# control_board.net
KiCad netlist of a schematic drawn in EAGLE
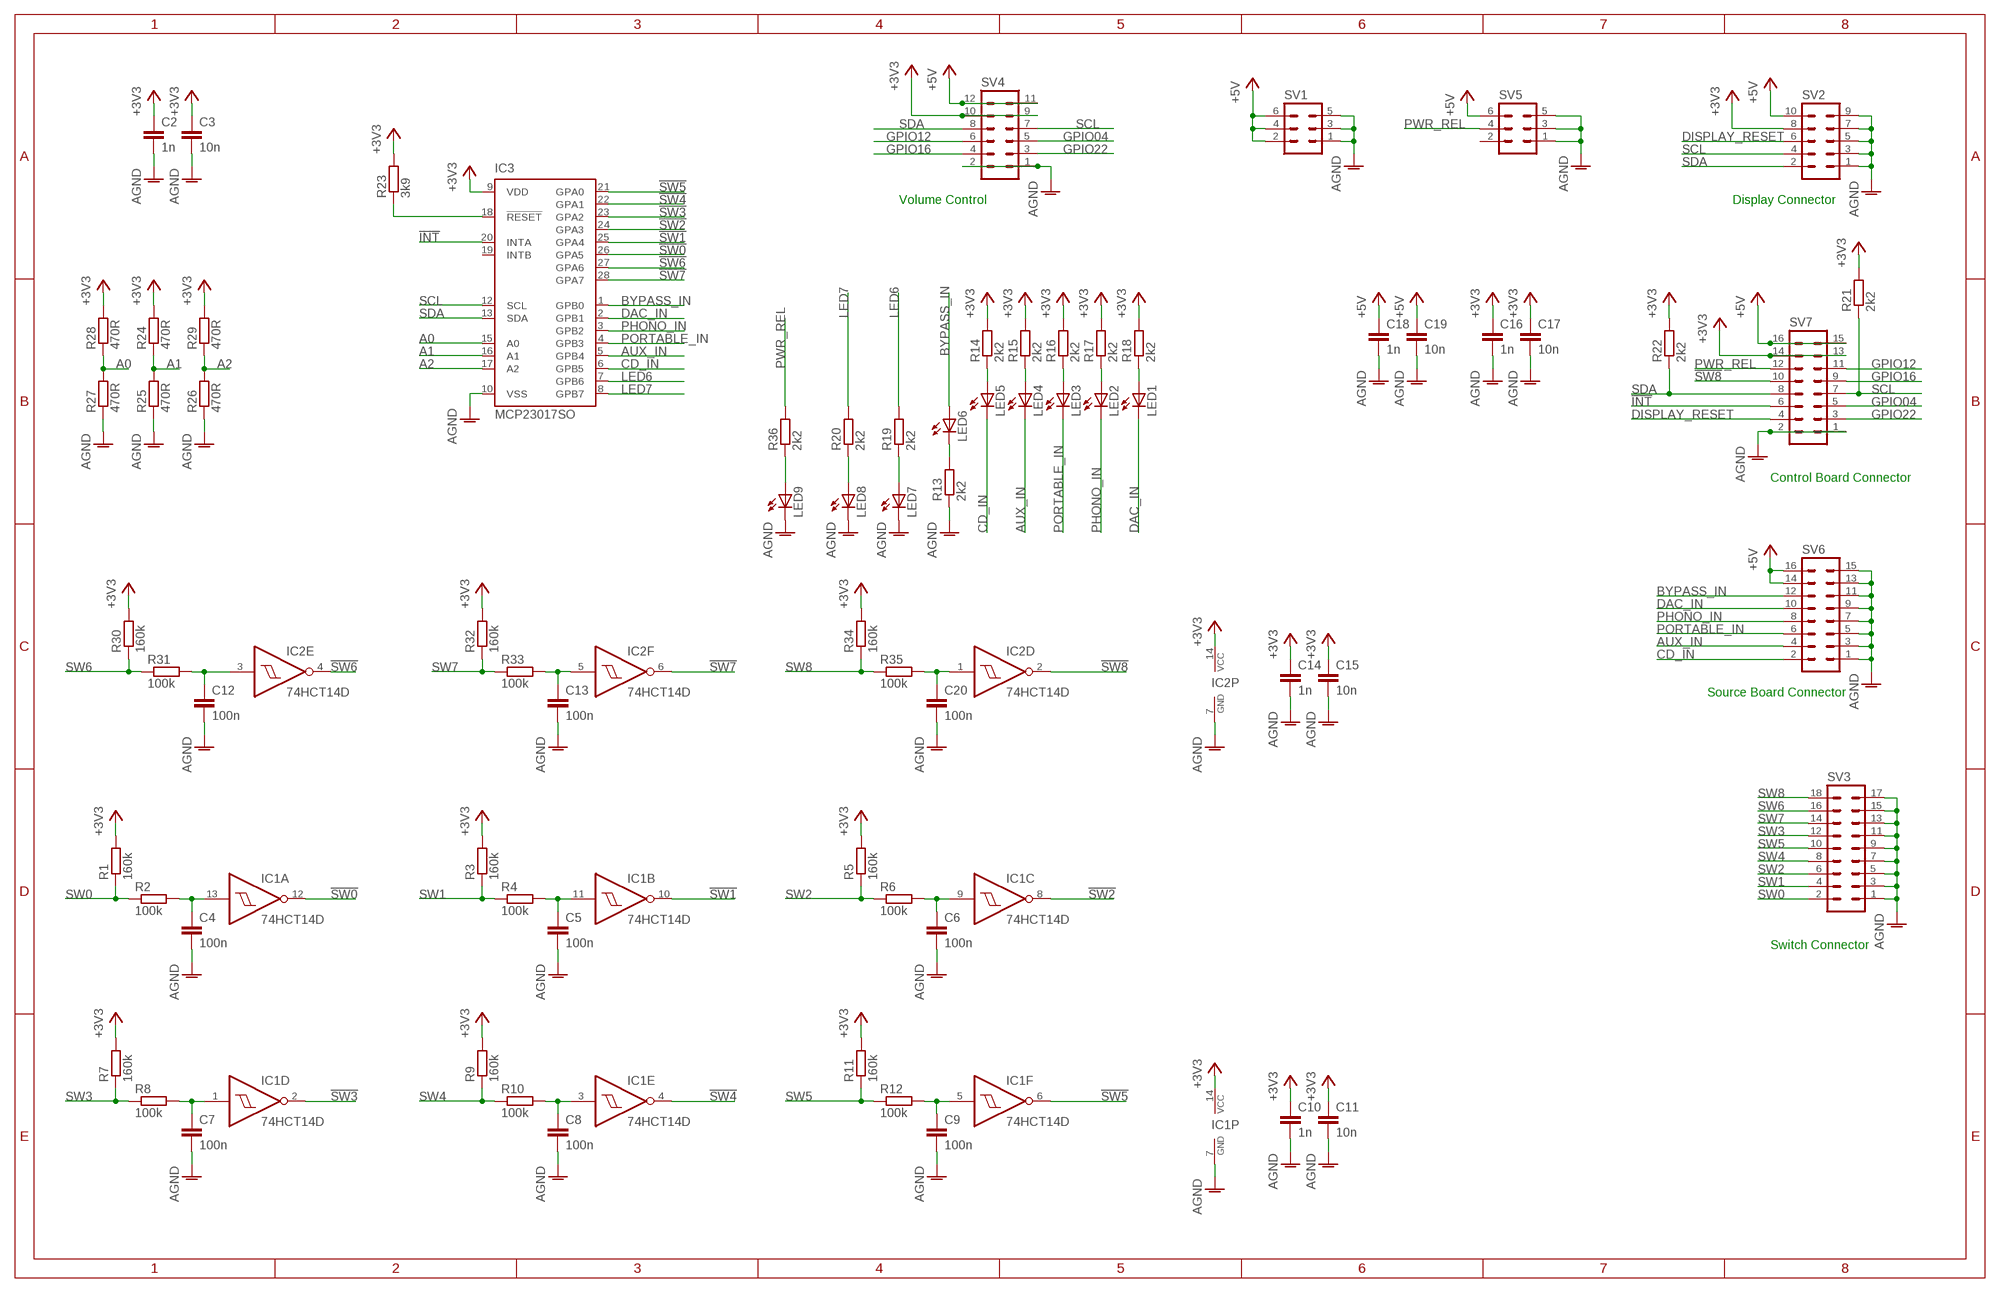
[diagram p0: schematic, sheet 1]

(export (version "E")
  (design (tool "Eeschema 10.0.6"))
  (components
    (comp (ref "C2")
      (value "1n")
      (footprint "eagle-import:C0603")
      (libsource (lib "eagle-import") (part "C-EUC0603"))
    )
    (comp (ref "C3")
      (value "10n")
      (footprint "eagle-import:C0603")
      (libsource (lib "eagle-import") (part "C-EUC0603"))
    )
    (comp (ref "C4")
      (value "100n")
      (footprint "eagle-import:C0603")
      (libsource (lib "eagle-import") (part "C-EUC0603"))
    )
    (comp (ref "C5")
      (value "100n")
      (footprint "eagle-import:C0603")
      (libsource (lib "eagle-import") (part "C-EUC0603"))
    )
    (comp (ref "C6")
      (value "100n")
      (footprint "eagle-import:C0603")
      (libsource (lib "eagle-import") (part "C-EUC0603"))
    )
    (comp (ref "C7")
      (value "100n")
      (footprint "eagle-import:C0603")
      (libsource (lib "eagle-import") (part "C-EUC0603"))
    )
    (comp (ref "C8")
      (value "100n")
      (footprint "eagle-import:C0603")
      (libsource (lib "eagle-import") (part "C-EUC0603"))
    )
    (comp (ref "C9")
      (value "100n")
      (footprint "eagle-import:C0603")
      (libsource (lib "eagle-import") (part "C-EUC0603"))
    )
    (comp (ref "C10")
      (value "1n")
      (footprint "eagle-import:C0603")
      (libsource (lib "eagle-import") (part "C-EUC0603"))
    )
    (comp (ref "C11")
      (value "10n")
      (footprint "eagle-import:C0603")
      (libsource (lib "eagle-import") (part "C-EUC0603"))
    )
    (comp (ref "C12")
      (value "100n")
      (footprint "eagle-import:C0603")
      (libsource (lib "eagle-import") (part "C-EUC0603"))
    )
    (comp (ref "C13")
      (value "100n")
      (footprint "eagle-import:C0603")
      (libsource (lib "eagle-import") (part "C-EUC0603"))
    )
    (comp (ref "C14")
      (value "1n")
      (footprint "eagle-import:C0603")
      (libsource (lib "eagle-import") (part "C-EUC0603"))
    )
    (comp (ref "C15")
      (value "10n")
      (footprint "eagle-import:C0603")
      (libsource (lib "eagle-import") (part "C-EUC0603"))
    )
    (comp (ref "C16")
      (value "1n")
      (footprint "eagle-import:C0603")
      (libsource (lib "eagle-import") (part "C-EUC0603"))
    )
    (comp (ref "C17")
      (value "10n")
      (footprint "eagle-import:C0603")
      (libsource (lib "eagle-import") (part "C-EUC0603"))
    )
    (comp (ref "C18")
      (value "1n")
      (footprint "eagle-import:C0603")
      (libsource (lib "eagle-import") (part "C-EUC0603"))
    )
    (comp (ref "C19")
      (value "10n")
      (footprint "eagle-import:C0603")
      (libsource (lib "eagle-import") (part "C-EUC0603"))
    )
    (comp (ref "C20")
      (value "100n")
      (footprint "eagle-import:C0603")
      (libsource (lib "eagle-import") (part "C-EUC0603"))
    )
    (comp (ref "IC1")
      (value "74HCT14D")
      (footprint "eagle-import:SO14")
      (libsource (lib "eagle-import") (part "7414DHCT"))
    )
    (comp (ref "IC2")
      (value "74HCT14D")
      (footprint "eagle-import:SO14")
      (libsource (lib "eagle-import") (part "7414DHCT"))
    )
    (comp (ref "IC3")
      (value "MCP23017SO")
      (footprint "eagle-import:SO28W")
      (fields (field (name "MF") "MICROCHIP") (field (name "MPN") "MCP23017-E/SO"))
      (libsource (lib "eagle-import") (part "MCP23017SO"))
    )
    (comp (ref "LED1")
      (value "LEDCHIPLED_0603")
      (footprint "eagle-import:CHIPLED_0603")
      (libsource (lib "eagle-import") (part "LEDCHIPLED_0603"))
    )
    (comp (ref "LED2")
      (value "LEDCHIPLED_0603")
      (footprint "eagle-import:CHIPLED_0603")
      (libsource (lib "eagle-import") (part "LEDCHIPLED_0603"))
    )
    (comp (ref "LED3")
      (value "LEDCHIPLED_0603")
      (footprint "eagle-import:CHIPLED_0603")
      (libsource (lib "eagle-import") (part "LEDCHIPLED_0603"))
    )
    (comp (ref "LED4")
      (value "LEDCHIPLED_0603")
      (footprint "eagle-import:CHIPLED_0603")
      (libsource (lib "eagle-import") (part "LEDCHIPLED_0603"))
    )
    (comp (ref "LED5")
      (value "LEDCHIPLED_0603")
      (footprint "eagle-import:CHIPLED_0603")
      (libsource (lib "eagle-import") (part "LEDCHIPLED_0603"))
    )
    (comp (ref "LED6")
      (value "LEDCHIPLED_0603")
      (footprint "eagle-import:CHIPLED_0603")
      (libsource (lib "eagle-import") (part "LEDCHIPLED_0603"))
    )
    (comp (ref "LED7")
      (value "LEDCHIPLED_0603")
      (footprint "eagle-import:CHIPLED_0603")
      (libsource (lib "eagle-import") (part "LEDCHIPLED_0603"))
    )
    (comp (ref "LED8")
      (value "LEDCHIPLED_0603")
      (footprint "eagle-import:CHIPLED_0603")
      (libsource (lib "eagle-import") (part "LEDCHIPLED_0603"))
    )
    (comp (ref "LED9")
      (value "LEDCHIPLED_0603")
      (footprint "eagle-import:CHIPLED_0603")
      (libsource (lib "eagle-import") (part "LEDCHIPLED_0603"))
    )
    (comp (ref "R1")
      (value "160k")
      (footprint "eagle-import:R0603")
      (libsource (lib "eagle-import") (part "R-EU_R0603"))
    )
    (comp (ref "R2")
      (value "100k")
      (footprint "eagle-import:R0603")
      (libsource (lib "eagle-import") (part "R-EU_R0603"))
    )
    (comp (ref "R3")
      (value "160k")
      (footprint "eagle-import:R0603")
      (libsource (lib "eagle-import") (part "R-EU_R0603"))
    )
    (comp (ref "R4")
      (value "100k")
      (footprint "eagle-import:R0603")
      (libsource (lib "eagle-import") (part "R-EU_R0603"))
    )
    (comp (ref "R5")
      (value "160k")
      (footprint "eagle-import:R0603")
      (libsource (lib "eagle-import") (part "R-EU_R0603"))
    )
    (comp (ref "R6")
      (value "100k")
      (footprint "eagle-import:R0603")
      (libsource (lib "eagle-import") (part "R-EU_R0603"))
    )
    (comp (ref "R7")
      (value "160k")
      (footprint "eagle-import:R0603")
      (libsource (lib "eagle-import") (part "R-EU_R0603"))
    )
    (comp (ref "R8")
      (value "100k")
      (footprint "eagle-import:R0603")
      (libsource (lib "eagle-import") (part "R-EU_R0603"))
    )
    (comp (ref "R9")
      (value "160k")
      (footprint "eagle-import:R0603")
      (libsource (lib "eagle-import") (part "R-EU_R0603"))
    )
    (comp (ref "R10")
      (value "100k")
      (footprint "eagle-import:R0603")
      (libsource (lib "eagle-import") (part "R-EU_R0603"))
    )
    (comp (ref "R11")
      (value "160k")
      (footprint "eagle-import:R0603")
      (libsource (lib "eagle-import") (part "R-EU_R0603"))
    )
    (comp (ref "R12")
      (value "100k")
      (footprint "eagle-import:R0603")
      (libsource (lib "eagle-import") (part "R-EU_R0603"))
    )
    (comp (ref "R13")
      (value "2k2")
      (footprint "eagle-import:R0603")
      (libsource (lib "eagle-import") (part "R-EU_R0603"))
    )
    (comp (ref "R14")
      (value "2k2")
      (footprint "eagle-import:R0603")
      (libsource (lib "eagle-import") (part "R-EU_R0603"))
    )
    (comp (ref "R15")
      (value "2k2")
      (footprint "eagle-import:R0603")
      (libsource (lib "eagle-import") (part "R-EU_R0603"))
    )
    (comp (ref "R16")
      (value "2k2")
      (footprint "eagle-import:R0603")
      (libsource (lib "eagle-import") (part "R-EU_R0603"))
    )
    (comp (ref "R17")
      (value "2k2")
      (footprint "eagle-import:R0603")
      (libsource (lib "eagle-import") (part "R-EU_R0603"))
    )
    (comp (ref "R18")
      (value "2k2")
      (footprint "eagle-import:R0603")
      (libsource (lib "eagle-import") (part "R-EU_R0603"))
    )
    (comp (ref "R19")
      (value "2k2")
      (footprint "eagle-import:R0603")
      (libsource (lib "eagle-import") (part "R-EU_R0603"))
    )
    (comp (ref "R20")
      (value "2k2")
      (footprint "eagle-import:R0603")
      (libsource (lib "eagle-import") (part "R-EU_R0603"))
    )
    (comp (ref "R21")
      (value "2k2")
      (footprint "eagle-import:R0603")
      (libsource (lib "eagle-import") (part "R-EU_R0603"))
    )
    (comp (ref "R22")
      (value "2k2")
      (footprint "eagle-import:R0603")
      (libsource (lib "eagle-import") (part "R-EU_R0603"))
    )
    (comp (ref "R23")
      (value "3k9")
      (footprint "eagle-import:R0603")
      (libsource (lib "eagle-import") (part "R-EU_R0603"))
    )
    (comp (ref "R24")
      (value "470R")
      (footprint "eagle-import:R0603")
      (libsource (lib "eagle-import") (part "R-EU_R0603"))
    )
    (comp (ref "R25")
      (value "470R")
      (footprint "eagle-import:R0603")
      (libsource (lib "eagle-import") (part "R-EU_R0603"))
    )
    (comp (ref "R26")
      (value "470R")
      (footprint "eagle-import:R0603")
      (libsource (lib "eagle-import") (part "R-EU_R0603"))
    )
    (comp (ref "R27")
      (value "470R")
      (footprint "eagle-import:R0603")
      (libsource (lib "eagle-import") (part "R-EU_R0603"))
    )
    (comp (ref "R28")
      (value "470R")
      (footprint "eagle-import:R0603")
      (libsource (lib "eagle-import") (part "R-EU_R0603"))
    )
    (comp (ref "R29")
      (value "470R")
      (footprint "eagle-import:R0603")
      (libsource (lib "eagle-import") (part "R-EU_R0603"))
    )
    (comp (ref "R30")
      (value "160k")
      (footprint "eagle-import:R0603")
      (libsource (lib "eagle-import") (part "R-EU_R0603"))
    )
    (comp (ref "R31")
      (value "100k")
      (footprint "eagle-import:R0603")
      (libsource (lib "eagle-import") (part "R-EU_R0603"))
    )
    (comp (ref "R32")
      (value "160k")
      (footprint "eagle-import:R0603")
      (libsource (lib "eagle-import") (part "R-EU_R0603"))
    )
    (comp (ref "R33")
      (value "100k")
      (footprint "eagle-import:R0603")
      (libsource (lib "eagle-import") (part "R-EU_R0603"))
    )
    (comp (ref "R34")
      (value "160k")
      (footprint "eagle-import:R0603")
      (libsource (lib "eagle-import") (part "R-EU_R0603"))
    )
    (comp (ref "R35")
      (value "100k")
      (footprint "eagle-import:R0603")
      (libsource (lib "eagle-import") (part "R-EU_R0603"))
    )
    (comp (ref "R36")
      (value "2k2")
      (footprint "eagle-import:R0603")
      (libsource (lib "eagle-import") (part "R-EU_R0603"))
    )
    (comp (ref "SV1")
      (value "MA03-2")
      (footprint "eagle-import:MA03-2")
      (libsource (lib "eagle-import") (part "MA03-2"))
    )
    (comp (ref "SV2")
      (value "MA05-2")
      (footprint "eagle-import:MA05-2")
      (libsource (lib "eagle-import") (part "MA05-2"))
    )
    (comp (ref "SV3")
      (value "MA09-2")
      (footprint "eagle-import:MA09-2")
      (libsource (lib "eagle-import") (part "MA09-2"))
    )
    (comp (ref "SV4")
      (value "MA06-2")
      (footprint "eagle-import:MA06-2")
      (libsource (lib "eagle-import") (part "MA06-2"))
    )
    (comp (ref "SV5")
      (value "MA03-2")
      (footprint "eagle-import:MA03-2")
      (libsource (lib "eagle-import") (part "MA03-2"))
    )
    (comp (ref "SV6")
      (value "MA08-2")
      (footprint "eagle-import:MA08-2")
      (libsource (lib "eagle-import") (part "MA08-2"))
    )
    (comp (ref "SV7")
      (value "MA08-2")
      (footprint "eagle-import:MA08-2")
      (libsource (lib "eagle-import") (part "MA08-2"))
    )
  )
  (nets
    (net (code "1") (name "+3V3") (class "Default")
      (node (ref "C10") (pin "1") (pinfunction "1_1") (pintype "passive"))
      (node (ref "C11") (pin "1") (pinfunction "1_1") (pintype "passive"))
      (node (ref "C14") (pin "1") (pinfunction "1_1") (pintype "passive"))
      (node (ref "C15") (pin "1") (pinfunction "1_1") (pintype "passive"))
      (node (ref "C16") (pin "1") (pinfunction "1_1") (pintype "passive"))
      (node (ref "C17") (pin "1") (pinfunction "1_1") (pintype "passive"))
      (node (ref "C2") (pin "1") (pinfunction "1_1") (pintype "passive"))
      (node (ref "C3") (pin "1") (pinfunction "1_1") (pintype "passive"))
      (node (ref "IC1") (pin "14") (pinfunction "VCC_14") (pintype "power_in"))
      (node (ref "IC2") (pin "14") (pinfunction "VCC_14") (pintype "power_in"))
      (node (ref "IC3") (pin "9") (pinfunction "VDD_9") (pintype "power_in"))
      (node (ref "R1") (pin "2") (pinfunction "2_2") (pintype "passive"))
      (node (ref "R11") (pin "2") (pinfunction "2_2") (pintype "passive"))
      (node (ref "R14") (pin "2") (pinfunction "2_2") (pintype "passive"))
      (node (ref "R15") (pin "2") (pinfunction "2_2") (pintype "passive"))
      (node (ref "R16") (pin "2") (pinfunction "2_2") (pintype "passive"))
      (node (ref "R17") (pin "2") (pinfunction "2_2") (pintype "passive"))
      (node (ref "R18") (pin "2") (pinfunction "2_2") (pintype "passive"))
      (node (ref "R21") (pin "2") (pinfunction "2_2") (pintype "passive"))
      (node (ref "R22") (pin "2") (pinfunction "2_2") (pintype "passive"))
      (node (ref "R23") (pin "2") (pinfunction "2_2") (pintype "passive"))
      (node (ref "R24") (pin "2") (pinfunction "2_2") (pintype "passive"))
      (node (ref "R28") (pin "2") (pinfunction "2_2") (pintype "passive"))
      (node (ref "R29") (pin "2") (pinfunction "2_2") (pintype "passive"))
      (node (ref "R3") (pin "2") (pinfunction "2_2") (pintype "passive"))
      (node (ref "R30") (pin "2") (pinfunction "2_2") (pintype "passive"))
      (node (ref "R32") (pin "2") (pinfunction "2_2") (pintype "passive"))
      (node (ref "R34") (pin "2") (pinfunction "2_2") (pintype "passive"))
      (node (ref "R5") (pin "2") (pinfunction "2_2") (pintype "passive"))
      (node (ref "R7") (pin "2") (pinfunction "2_2") (pintype "passive"))
      (node (ref "R9") (pin "2") (pinfunction "2_2") (pintype "passive"))
      (node (ref "SV2") (pin "8") (pinfunction "8_8") (pintype "passive"))
      (node (ref "SV4") (pin "10") (pinfunction "10_10") (pintype "passive"))
      (node (ref "SV4") (pin "9") (pinfunction "9_9") (pintype "passive"))
      (node (ref "SV7") (pin "13") (pinfunction "13_13") (pintype "passive"))
      (node (ref "SV7") (pin "14") (pinfunction "14_14") (pintype "passive"))
    )
    (net (code "2") (name "+5V") (class "Default")
      (node (ref "C18") (pin "1") (pinfunction "1_1") (pintype "passive"))
      (node (ref "C19") (pin "1") (pinfunction "1_1") (pintype "passive"))
      (node (ref "SV1") (pin "2") (pinfunction "2_2") (pintype "passive"))
      (node (ref "SV1") (pin "4") (pinfunction "4_4") (pintype "passive"))
      (node (ref "SV1") (pin "6") (pinfunction "6_6") (pintype "passive"))
      (node (ref "SV2") (pin "10") (pinfunction "10_10") (pintype "passive"))
      (node (ref "SV4") (pin "11") (pinfunction "11_11") (pintype "passive"))
      (node (ref "SV4") (pin "12") (pinfunction "12_12") (pintype "passive"))
      (node (ref "SV5") (pin "6") (pinfunction "6_6") (pintype "passive"))
      (node (ref "SV6") (pin "14") (pinfunction "14_14") (pintype "passive"))
      (node (ref "SV6") (pin "16") (pinfunction "16_16") (pintype "passive"))
      (node (ref "SV7") (pin "15") (pinfunction "15_15") (pintype "passive"))
      (node (ref "SV7") (pin "16") (pinfunction "16_16") (pintype "passive"))
    )
    (net (code "3") (name "/A0") (class "Default")
      (node (ref "IC3") (pin "15") (pinfunction "A0_15") (pintype "input"))
      (node (ref "R27") (pin "2") (pinfunction "2_2") (pintype "passive"))
      (node (ref "R28") (pin "1") (pinfunction "1_1") (pintype "passive"))
    )
    (net (code "4") (name "/A1") (class "Default")
      (node (ref "IC3") (pin "16") (pinfunction "A1_16") (pintype "input"))
      (node (ref "R24") (pin "1") (pinfunction "1_1") (pintype "passive"))
      (node (ref "R25") (pin "2") (pinfunction "2_2") (pintype "passive"))
    )
    (net (code "5") (name "/A2") (class "Default")
      (node (ref "IC3") (pin "17") (pinfunction "A2_17") (pintype "input"))
      (node (ref "R26") (pin "2") (pinfunction "2_2") (pintype "passive"))
      (node (ref "R29") (pin "1") (pinfunction "1_1") (pintype "passive"))
    )
    (net (code "6") (name "/AUX_IN") (class "Default")
      (node (ref "IC3") (pin "5") (pinfunction "GPB4_5") (pintype "bidirectional"))
      (node (ref "LED4") (pin "C") (pinfunction "C_C") (pintype "passive"))
      (node (ref "SV6") (pin "4") (pinfunction "4_4") (pintype "passive"))
    )
    (net (code "7") (name "/BYPASS_IN") (class "Default")
      (node (ref "IC3") (pin "1") (pinfunction "GPB0_1") (pintype "bidirectional"))
      (node (ref "LED6") (pin "A") (pinfunction "A_A") (pintype "passive"))
      (node (ref "SV6") (pin "12") (pinfunction "12_12") (pintype "passive"))
    )
    (net (code "8") (name "/CD_IN") (class "Default")
      (node (ref "IC3") (pin "6") (pinfunction "GPB5_6") (pintype "bidirectional"))
      (node (ref "LED5") (pin "C") (pinfunction "C_C") (pintype "passive"))
      (node (ref "SV6") (pin "2") (pinfunction "2_2") (pintype "passive"))
    )
    (net (code "9") (name "/DAC_IN") (class "Default")
      (node (ref "IC3") (pin "2") (pinfunction "GPB1_2") (pintype "bidirectional"))
      (node (ref "LED1") (pin "C") (pinfunction "C_C") (pintype "passive"))
      (node (ref "SV6") (pin "10") (pinfunction "10_10") (pintype "passive"))
    )
    (net (code "10") (name "/DISPLAY_RESET") (class "Default")
      (node (ref "SV2") (pin "6") (pinfunction "6_6") (pintype "passive"))
      (node (ref "SV7") (pin "4") (pinfunction "4_4") (pintype "passive"))
    )
    (net (code "11") (name "/GPIO04") (class "Default")
      (node (ref "SV4") (pin "5") (pinfunction "5_5") (pintype "passive"))
      (node (ref "SV7") (pin "5") (pinfunction "5_5") (pintype "passive"))
    )
    (net (code "12") (name "/GPIO12") (class "Default")
      (node (ref "SV4") (pin "6") (pinfunction "6_6") (pintype "passive"))
      (node (ref "SV7") (pin "11") (pinfunction "11_11") (pintype "passive"))
    )
    (net (code "13") (name "/GPIO16") (class "Default")
      (node (ref "SV4") (pin "4") (pinfunction "4_4") (pintype "passive"))
      (node (ref "SV7") (pin "9") (pinfunction "9_9") (pintype "passive"))
    )
    (net (code "14") (name "/GPIO22") (class "Default")
      (node (ref "SV4") (pin "3") (pinfunction "3_3") (pintype "passive"))
      (node (ref "SV7") (pin "3") (pinfunction "3_3") (pintype "passive"))
    )
    (net (code "15") (name "/LED6") (class "Default")
      (node (ref "IC3") (pin "7") (pinfunction "GPB6_7") (pintype "bidirectional"))
      (node (ref "R19") (pin "2") (pinfunction "2_2") (pintype "passive"))
    )
    (net (code "16") (name "/LED7") (class "Default")
      (node (ref "IC3") (pin "8") (pinfunction "GPB7_8") (pintype "bidirectional"))
      (node (ref "R20") (pin "2") (pinfunction "2_2") (pintype "passive"))
    )
    (net (code "17") (name "/PHONO_IN") (class "Default")
      (node (ref "IC3") (pin "3") (pinfunction "GPB2_3") (pintype "bidirectional"))
      (node (ref "LED2") (pin "C") (pinfunction "C_C") (pintype "passive"))
      (node (ref "SV6") (pin "8") (pinfunction "8_8") (pintype "passive"))
    )
    (net (code "18") (name "/PORTABLE_IN") (class "Default")
      (node (ref "IC3") (pin "4") (pinfunction "GPB3_4") (pintype "bidirectional"))
      (node (ref "LED3") (pin "C") (pinfunction "C_C") (pintype "passive"))
      (node (ref "SV6") (pin "6") (pinfunction "6_6") (pintype "passive"))
    )
    (net (code "19") (name "/PWR_REL") (class "Default")
      (node (ref "R36") (pin "2") (pinfunction "2_2") (pintype "passive"))
      (node (ref "SV5") (pin "4") (pinfunction "4_4") (pintype "passive"))
      (node (ref "SV7") (pin "12") (pinfunction "12_12") (pintype "passive"))
    )
    (net (code "20") (name "/SCL") (class "Default")
      (node (ref "IC3") (pin "12") (pinfunction "SCL_12") (pintype "input"))
      (node (ref "R21") (pin "1") (pinfunction "1_1") (pintype "passive"))
      (node (ref "SV2") (pin "4") (pinfunction "4_4") (pintype "passive"))
      (node (ref "SV4") (pin "7") (pinfunction "7_7") (pintype "passive"))
      (node (ref "SV7") (pin "7") (pinfunction "7_7") (pintype "passive"))
    )
    (net (code "21") (name "/SDA") (class "Default")
      (node (ref "IC3") (pin "13") (pinfunction "SDA_13") (pintype "bidirectional"))
      (node (ref "R22") (pin "1") (pinfunction "1_1") (pintype "passive"))
      (node (ref "SV2") (pin "2") (pinfunction "2_2") (pintype "passive"))
      (node (ref "SV4") (pin "8") (pinfunction "8_8") (pintype "passive"))
      (node (ref "SV7") (pin "8") (pinfunction "8_8") (pintype "passive"))
    )
    (net (code "22") (name "/SW0") (class "Default")
      (node (ref "R1") (pin "1") (pinfunction "1_1") (pintype "passive"))
      (node (ref "R2") (pin "1") (pinfunction "1_1") (pintype "passive"))
      (node (ref "SV3") (pin "2") (pinfunction "2_2") (pintype "passive"))
    )
    (net (code "23") (name "/SW1") (class "Default")
      (node (ref "R3") (pin "1") (pinfunction "1_1") (pintype "passive"))
      (node (ref "R4") (pin "1") (pinfunction "1_1") (pintype "passive"))
      (node (ref "SV3") (pin "4") (pinfunction "4_4") (pintype "passive"))
    )
    (net (code "24") (name "/SW2") (class "Default")
      (node (ref "R5") (pin "1") (pinfunction "1_1") (pintype "passive"))
      (node (ref "R6") (pin "1") (pinfunction "1_1") (pintype "passive"))
      (node (ref "SV3") (pin "6") (pinfunction "6_6") (pintype "passive"))
    )
    (net (code "25") (name "/SW3") (class "Default")
      (node (ref "R7") (pin "1") (pinfunction "1_1") (pintype "passive"))
      (node (ref "R8") (pin "1") (pinfunction "1_1") (pintype "passive"))
      (node (ref "SV3") (pin "12") (pinfunction "12_12") (pintype "passive"))
    )
    (net (code "26") (name "/SW4") (class "Default")
      (node (ref "R10") (pin "1") (pinfunction "1_1") (pintype "passive"))
      (node (ref "R9") (pin "1") (pinfunction "1_1") (pintype "passive"))
      (node (ref "SV3") (pin "8") (pinfunction "8_8") (pintype "passive"))
    )
    (net (code "27") (name "/SW5") (class "Default")
      (node (ref "R11") (pin "1") (pinfunction "1_1") (pintype "passive"))
      (node (ref "R12") (pin "1") (pinfunction "1_1") (pintype "passive"))
      (node (ref "SV3") (pin "10") (pinfunction "10_10") (pintype "passive"))
    )
    (net (code "28") (name "/SW6") (class "Default")
      (node (ref "R30") (pin "1") (pinfunction "1_1") (pintype "passive"))
      (node (ref "R31") (pin "1") (pinfunction "1_1") (pintype "passive"))
      (node (ref "SV3") (pin "16") (pinfunction "16_16") (pintype "passive"))
    )
    (net (code "29") (name "/SW7") (class "Default")
      (node (ref "R32") (pin "1") (pinfunction "1_1") (pintype "passive"))
      (node (ref "R33") (pin "1") (pinfunction "1_1") (pintype "passive"))
      (node (ref "SV3") (pin "14") (pinfunction "14_14") (pintype "passive"))
    )
    (net (code "30") (name "/SW8") (class "Default")
      (node (ref "R34") (pin "1") (pinfunction "1_1") (pintype "passive"))
      (node (ref "R35") (pin "1") (pinfunction "1_1") (pintype "passive"))
      (node (ref "SV3") (pin "18") (pinfunction "18_18") (pintype "passive"))
    )
    (net (code "31") (name "/~{INT}") (class "Default")
      (node (ref "IC3") (pin "20") (pinfunction "INTA_20") (pintype "output"))
      (node (ref "SV7") (pin "6") (pinfunction "6_6") (pintype "passive"))
    )
    (net (code "32") (name "/~{SW0}") (class "Default")
      (node (ref "IC1") (pin "12") (pinfunction "O_12") (pintype "output"))
      (node (ref "IC3") (pin "26") (pinfunction "GPA5_26") (pintype "bidirectional"))
    )
    (net (code "33") (name "/~{SW1}") (class "Default")
      (node (ref "IC1") (pin "10") (pinfunction "O_10") (pintype "output"))
      (node (ref "IC3") (pin "25") (pinfunction "GPA4_25") (pintype "bidirectional"))
    )
    (net (code "34") (name "/~{SW2}") (class "Default")
      (node (ref "IC1") (pin "8") (pinfunction "O_8") (pintype "output"))
      (node (ref "IC3") (pin "24") (pinfunction "GPA3_24") (pintype "bidirectional"))
    )
    (net (code "35") (name "/~{SW3}") (class "Default")
      (node (ref "IC1") (pin "2") (pinfunction "O_2") (pintype "output"))
      (node (ref "IC3") (pin "23") (pinfunction "GPA2_23") (pintype "bidirectional"))
    )
    (net (code "36") (name "/~{SW4}") (class "Default")
      (node (ref "IC1") (pin "4") (pinfunction "O_4") (pintype "output"))
      (node (ref "IC3") (pin "22") (pinfunction "GPA1_22") (pintype "bidirectional"))
    )
    (net (code "37") (name "/~{SW5}") (class "Default")
      (node (ref "IC1") (pin "6") (pinfunction "O_6") (pintype "output"))
      (node (ref "IC3") (pin "21") (pinfunction "GPA0_21") (pintype "bidirectional"))
    )
    (net (code "38") (name "/~{SW6}") (class "Default")
      (node (ref "IC2") (pin "4") (pinfunction "O_4") (pintype "output"))
      (node (ref "IC3") (pin "27") (pinfunction "GPA6_27") (pintype "bidirectional"))
    )
    (net (code "39") (name "/~{SW7}") (class "Default")
      (node (ref "IC2") (pin "6") (pinfunction "O_6") (pintype "output"))
      (node (ref "IC3") (pin "28") (pinfunction "GPA7_28") (pintype "bidirectional"))
    )
    (net (code "40") (name "/~{SW8}") (class "Default")
      (node (ref "IC2") (pin "2") (pinfunction "O_2") (pintype "output"))
      (node (ref "SV7") (pin "10") (pinfunction "10_10") (pintype "passive"))
    )
    (net (code "41") (name "AGND") (class "Default")
      (node (ref "C10") (pin "2") (pinfunction "2_2") (pintype "passive"))
      (node (ref "C11") (pin "2") (pinfunction "2_2") (pintype "passive"))
      (node (ref "C12") (pin "2") (pinfunction "2_2") (pintype "passive"))
      (node (ref "C13") (pin "2") (pinfunction "2_2") (pintype "passive"))
      (node (ref "C14") (pin "2") (pinfunction "2_2") (pintype "passive"))
      (node (ref "C15") (pin "2") (pinfunction "2_2") (pintype "passive"))
      (node (ref "C16") (pin "2") (pinfunction "2_2") (pintype "passive"))
      (node (ref "C17") (pin "2") (pinfunction "2_2") (pintype "passive"))
      (node (ref "C18") (pin "2") (pinfunction "2_2") (pintype "passive"))
      (node (ref "C19") (pin "2") (pinfunction "2_2") (pintype "passive"))
      (node (ref "C2") (pin "2") (pinfunction "2_2") (pintype "passive"))
      (node (ref "C20") (pin "2") (pinfunction "2_2") (pintype "passive"))
      (node (ref "C3") (pin "2") (pinfunction "2_2") (pintype "passive"))
      (node (ref "C4") (pin "2") (pinfunction "2_2") (pintype "passive"))
      (node (ref "C5") (pin "2") (pinfunction "2_2") (pintype "passive"))
      (node (ref "C6") (pin "2") (pinfunction "2_2") (pintype "passive"))
      (node (ref "C7") (pin "2") (pinfunction "2_2") (pintype "passive"))
      (node (ref "C8") (pin "2") (pinfunction "2_2") (pintype "passive"))
      (node (ref "C9") (pin "2") (pinfunction "2_2") (pintype "passive"))
      (node (ref "IC1") (pin "7") (pinfunction "GND_7") (pintype "power_in"))
      (node (ref "IC2") (pin "7") (pinfunction "GND_7") (pintype "power_in"))
      (node (ref "IC3") (pin "10") (pinfunction "VSS_10") (pintype "power_in"))
      (node (ref "LED7") (pin "C") (pinfunction "C_C") (pintype "passive"))
      (node (ref "LED8") (pin "C") (pinfunction "C_C") (pintype "passive"))
      (node (ref "LED9") (pin "C") (pinfunction "C_C") (pintype "passive"))
      (node (ref "R13") (pin "1") (pinfunction "1_1") (pintype "passive"))
      (node (ref "R25") (pin "1") (pinfunction "1_1") (pintype "passive"))
      (node (ref "R26") (pin "1") (pinfunction "1_1") (pintype "passive"))
      (node (ref "R27") (pin "1") (pinfunction "1_1") (pintype "passive"))
      (node (ref "SV1") (pin "1") (pinfunction "1_1") (pintype "passive"))
      (node (ref "SV1") (pin "3") (pinfunction "3_3") (pintype "passive"))
      (node (ref "SV1") (pin "5") (pinfunction "5_5") (pintype "passive"))
      (node (ref "SV2") (pin "1") (pinfunction "1_1") (pintype "passive"))
      (node (ref "SV2") (pin "3") (pinfunction "3_3") (pintype "passive"))
      (node (ref "SV2") (pin "5") (pinfunction "5_5") (pintype "passive"))
      (node (ref "SV2") (pin "7") (pinfunction "7_7") (pintype "passive"))
      (node (ref "SV2") (pin "9") (pinfunction "9_9") (pintype "passive"))
      (node (ref "SV3") (pin "1") (pinfunction "1_1") (pintype "passive"))
      (node (ref "SV3") (pin "11") (pinfunction "11_11") (pintype "passive"))
      (node (ref "SV3") (pin "13") (pinfunction "13_13") (pintype "passive"))
      (node (ref "SV3") (pin "15") (pinfunction "15_15") (pintype "passive"))
      (node (ref "SV3") (pin "17") (pinfunction "17_17") (pintype "passive"))
      (node (ref "SV3") (pin "3") (pinfunction "3_3") (pintype "passive"))
      (node (ref "SV3") (pin "5") (pinfunction "5_5") (pintype "passive"))
      (node (ref "SV3") (pin "7") (pinfunction "7_7") (pintype "passive"))
      (node (ref "SV3") (pin "9") (pinfunction "9_9") (pintype "passive"))
      (node (ref "SV4") (pin "1") (pinfunction "1_1") (pintype "passive"))
      (node (ref "SV4") (pin "2") (pinfunction "2_2") (pintype "passive"))
      (node (ref "SV5") (pin "1") (pinfunction "1_1") (pintype "passive"))
      (node (ref "SV5") (pin "3") (pinfunction "3_3") (pintype "passive"))
      (node (ref "SV5") (pin "5") (pinfunction "5_5") (pintype "passive"))
      (node (ref "SV6") (pin "1") (pinfunction "1_1") (pintype "passive"))
      (node (ref "SV6") (pin "11") (pinfunction "11_11") (pintype "passive"))
      (node (ref "SV6") (pin "13") (pinfunction "13_13") (pintype "passive"))
      (node (ref "SV6") (pin "15") (pinfunction "15_15") (pintype "passive"))
      (node (ref "SV6") (pin "3") (pinfunction "3_3") (pintype "passive"))
      (node (ref "SV6") (pin "5") (pinfunction "5_5") (pintype "passive"))
      (node (ref "SV6") (pin "7") (pinfunction "7_7") (pintype "passive"))
      (node (ref "SV6") (pin "9") (pinfunction "9_9") (pintype "passive"))
      (node (ref "SV7") (pin "1") (pinfunction "1_1") (pintype "passive"))
      (node (ref "SV7") (pin "2") (pinfunction "2_2") (pintype "passive"))
    )
    (net (code "42") (name "Net-(IC1A-I)") (class "Default")
      (node (ref "C4") (pin "1") (pinfunction "1_1") (pintype "passive"))
      (node (ref "IC1") (pin "13") (pinfunction "I_13") (pintype "input"))
      (node (ref "R2") (pin "2") (pinfunction "2_2") (pintype "passive"))
    )
    (net (code "43") (name "Net-(IC1B-I)") (class "Default")
      (node (ref "C5") (pin "1") (pinfunction "1_1") (pintype "passive"))
      (node (ref "IC1") (pin "11") (pinfunction "I_11") (pintype "input"))
      (node (ref "R4") (pin "2") (pinfunction "2_2") (pintype "passive"))
    )
    (net (code "44") (name "Net-(IC1C-I)") (class "Default")
      (node (ref "C6") (pin "1") (pinfunction "1_1") (pintype "passive"))
      (node (ref "IC1") (pin "9") (pinfunction "I_9") (pintype "input"))
      (node (ref "R6") (pin "2") (pinfunction "2_2") (pintype "passive"))
    )
    (net (code "45") (name "Net-(IC1D-I)") (class "Default")
      (node (ref "C7") (pin "1") (pinfunction "1_1") (pintype "passive"))
      (node (ref "IC1") (pin "1") (pinfunction "I_1") (pintype "input"))
      (node (ref "R8") (pin "2") (pinfunction "2_2") (pintype "passive"))
    )
    (net (code "46") (name "Net-(IC1E-I)") (class "Default")
      (node (ref "C8") (pin "1") (pinfunction "1_1") (pintype "passive"))
      (node (ref "IC1") (pin "3") (pinfunction "I_3") (pintype "input"))
      (node (ref "R10") (pin "2") (pinfunction "2_2") (pintype "passive"))
    )
    (net (code "47") (name "Net-(IC1F-I)") (class "Default")
      (node (ref "C9") (pin "1") (pinfunction "1_1") (pintype "passive"))
      (node (ref "IC1") (pin "5") (pinfunction "I_5") (pintype "input"))
      (node (ref "R12") (pin "2") (pinfunction "2_2") (pintype "passive"))
    )
    (net (code "48") (name "Net-(IC2D-I)") (class "Default")
      (node (ref "C20") (pin "1") (pinfunction "1_1") (pintype "passive"))
      (node (ref "IC2") (pin "1") (pinfunction "I_1") (pintype "input"))
      (node (ref "R35") (pin "2") (pinfunction "2_2") (pintype "passive"))
    )
    (net (code "49") (name "Net-(IC2E-I)") (class "Default")
      (node (ref "C12") (pin "1") (pinfunction "1_1") (pintype "passive"))
      (node (ref "IC2") (pin "3") (pinfunction "I_3") (pintype "input"))
      (node (ref "R31") (pin "2") (pinfunction "2_2") (pintype "passive"))
    )
    (net (code "50") (name "Net-(IC2F-I)") (class "Default")
      (node (ref "C13") (pin "1") (pinfunction "1_1") (pintype "passive"))
      (node (ref "IC2") (pin "5") (pinfunction "I_5") (pintype "input"))
      (node (ref "R33") (pin "2") (pinfunction "2_2") (pintype "passive"))
    )
    (net (code "51") (name "Net-(IC3-~{RESET})") (class "Default")
      (node (ref "IC3") (pin "18") (pinfunction "~{RESET}_18") (pintype "input"))
      (node (ref "R23") (pin "1") (pinfunction "1_1") (pintype "passive"))
    )
    (net (code "52") (name "Net-(LED1-PadA)") (class "Default")
      (node (ref "LED1") (pin "A") (pinfunction "A_A") (pintype "passive"))
      (node (ref "R18") (pin "1") (pinfunction "1_1") (pintype "passive"))
    )
    (net (code "53") (name "Net-(LED2-PadA)") (class "Default")
      (node (ref "LED2") (pin "A") (pinfunction "A_A") (pintype "passive"))
      (node (ref "R17") (pin "1") (pinfunction "1_1") (pintype "passive"))
    )
    (net (code "54") (name "Net-(LED3-PadA)") (class "Default")
      (node (ref "LED3") (pin "A") (pinfunction "A_A") (pintype "passive"))
      (node (ref "R16") (pin "1") (pinfunction "1_1") (pintype "passive"))
    )
    (net (code "55") (name "Net-(LED4-PadA)") (class "Default")
      (node (ref "LED4") (pin "A") (pinfunction "A_A") (pintype "passive"))
      (node (ref "R15") (pin "1") (pinfunction "1_1") (pintype "passive"))
    )
    (net (code "56") (name "Net-(LED5-PadA)") (class "Default")
      (node (ref "LED5") (pin "A") (pinfunction "A_A") (pintype "passive"))
      (node (ref "R14") (pin "1") (pinfunction "1_1") (pintype "passive"))
    )
    (net (code "57") (name "Net-(LED6-PadC)") (class "Default")
      (node (ref "LED6") (pin "C") (pinfunction "C_C") (pintype "passive"))
      (node (ref "R13") (pin "2") (pinfunction "2_2") (pintype "passive"))
    )
    (net (code "58") (name "Net-(LED7-PadA)") (class "Default")
      (node (ref "LED7") (pin "A") (pinfunction "A_A") (pintype "passive"))
      (node (ref "R19") (pin "1") (pinfunction "1_1") (pintype "passive"))
    )
    (net (code "59") (name "Net-(LED8-PadA)") (class "Default")
      (node (ref "LED8") (pin "A") (pinfunction "A_A") (pintype "passive"))
      (node (ref "R20") (pin "1") (pinfunction "1_1") (pintype "passive"))
    )
    (net (code "60") (name "Net-(LED9-PadA)") (class "Default")
      (node (ref "LED9") (pin "A") (pinfunction "A_A") (pintype "passive"))
      (node (ref "R36") (pin "1") (pinfunction "1_1") (pintype "passive"))
    )
    (net (code "61") (name "unconnected-(IC3-INTB-Pad19)") (class "Default")
      (node (ref "IC3") (pin "19") (pinfunction "INTB_19") (pintype "output"))
    )
    (net (code "62") (name "unconnected-(SV5-Pad2)") (class "Default")
      (node (ref "SV5") (pin "2") (pinfunction "2_2") (pintype "passive"))
    )
  )
)
